# Schematic.net
KiCad netlist of a schematic drawn in EAGLE
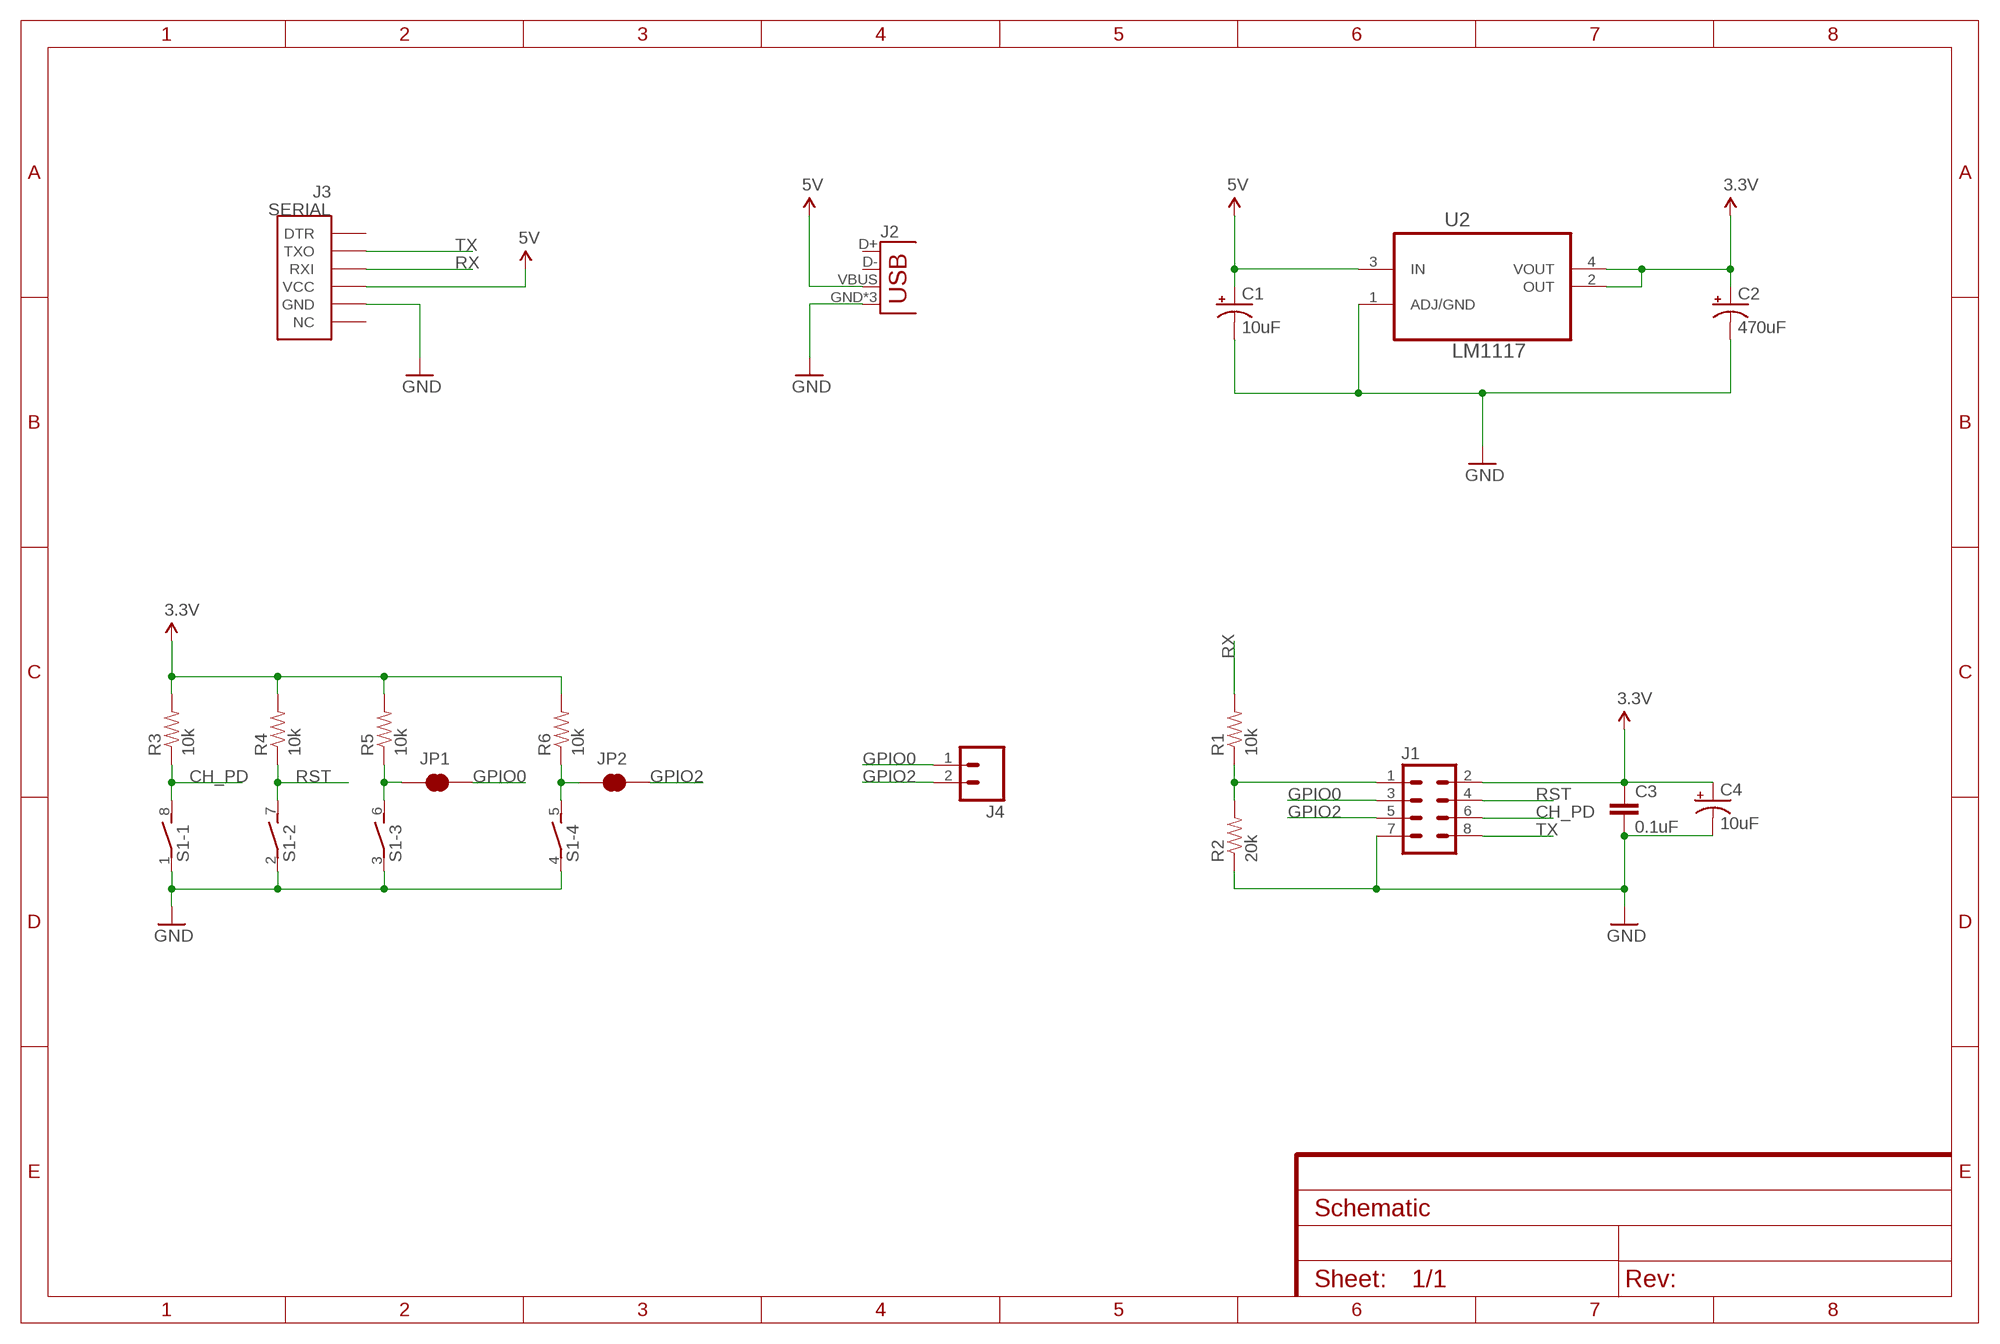
[diagram p0: schematic, sheet 1]

(export (version "E")
  (design (tool "Eeschema 10.0.6"))
  (components
    (comp (ref "C1")
      (value "10uF")
      (footprint "eagle-import:EIA3216-KIT")
      (libsource (lib "eagle-import") (part "CAP_POL1206-KIT"))
    )
    (comp (ref "C2")
      (value "470uF")
      (footprint "eagle-import:CPOL-RADIAL-100UF-25V")
      (libsource (lib "eagle-import") (part "CAP_POLPTH1"))
    )
    (comp (ref "C3")
      (value "0.1uF")
      (footprint "eagle-import:1206")
      (libsource (lib "eagle-import") (part "CAP1206"))
    )
    (comp (ref "C4")
      (value "10uF")
      (footprint "eagle-import:EIA3216-KIT")
      (libsource (lib "eagle-import") (part "CAP_POL1206-KIT"))
    )
    (comp (ref "J1")
      (value "M04X2")
      (footprint "eagle-import:2X4")
      (libsource (lib "eagle-import") (part "M04X2"))
    )
    (comp (ref "J2")
      (value "USB-MICROB")
      (footprint "eagle-import:USB-MICROB")
      (libsource (lib "eagle-import") (part "USB-MICROB"))
    )
    (comp (ref "J3")
      (value "SERIAL")
      (footprint "eagle-import:CP2102_DEVICE_SIDE")
      (libsource (lib "eagle-import") (part "CP2102_DEVICECP"))
    )
    (comp (ref "J4")
      (value "M02LOCK")
      (footprint "eagle-import:1X02_LOCK")
      (libsource (lib "eagle-import") (part "M02LOCK"))
    )
    (comp (ref "JP1")
      (value "JUMPER-PAD-2-NC_BY_TRACE")
      (footprint "eagle-import:PAD-JUMPER-2-NC_BY_TRACE_YES_SILK")
      (libsource (lib "eagle-import") (part "JUMPER-PAD-2-NC_BY_TRACE"))
    )
    (comp (ref "JP2")
      (value "JUMPER-PAD-2-NC_BY_TRACE")
      (footprint "eagle-import:PAD-JUMPER-2-NC_BY_TRACE_YES_SILK")
      (libsource (lib "eagle-import") (part "JUMPER-PAD-2-NC_BY_TRACE"))
    )
    (comp (ref "R1")
      (value "10k")
      (footprint "eagle-import:1206")
      (libsource (lib "eagle-import") (part "RESISTOR1206"))
    )
    (comp (ref "R2")
      (value "20k")
      (footprint "eagle-import:1206")
      (libsource (lib "eagle-import") (part "RESISTOR1206"))
    )
    (comp (ref "R3")
      (value "10k")
      (footprint "eagle-import:1206")
      (libsource (lib "eagle-import") (part "RESISTOR1206"))
    )
    (comp (ref "R4")
      (value "10k")
      (footprint "eagle-import:1206")
      (libsource (lib "eagle-import") (part "RESISTOR1206"))
    )
    (comp (ref "R5")
      (value "10k")
      (footprint "eagle-import:1206")
      (libsource (lib "eagle-import") (part "RESISTOR1206"))
    )
    (comp (ref "R6")
      (value "10k")
      (footprint "eagle-import:1206")
      (libsource (lib "eagle-import") (part "RESISTOR1206"))
    )
    (comp (ref "S1")
      (value "DIP04S")
      (footprint "eagle-import:DIP04S")
      (libsource (lib "eagle-import") (part "DIP04S"))
    )
    (comp (ref "U2")
      (value "LM1117")
      (footprint "eagle-import:SOT230P696X180-4N")
      (fields (field (name "MPN") "LM1117MP-3.3"))
      (libsource (lib "eagle-import") (part "LM1117MP-3.3"))
    )
  )
  (nets
    (net (code "1") (name "/CH_PD") (class "Default")
      (node (ref "J1") (pin "6") (pinfunction "6_6") (pintype "passive"))
      (node (ref "R3") (pin "1") (pinfunction "1_1") (pintype "passive"))
      (node (ref "S1") (pin "8") (pinfunction "2_8") (pintype "passive"))
    )
    (net (code "2") (name "/GPIO0") (class "Default")
      (node (ref "J1") (pin "3") (pinfunction "3_3") (pintype "passive"))
      (node (ref "J4") (pin "1") (pinfunction "1_1") (pintype "passive"))
      (node (ref "JP1") (pin "2") (pinfunction "2_2") (pintype "passive"))
    )
    (net (code "3") (name "/GPIO2") (class "Default")
      (node (ref "J1") (pin "5") (pinfunction "5_5") (pintype "passive"))
      (node (ref "J4") (pin "2") (pinfunction "2_2") (pintype "passive"))
      (node (ref "JP2") (pin "2") (pinfunction "2_2") (pintype "passive"))
    )
    (net (code "4") (name "/RST") (class "Default")
      (node (ref "J1") (pin "4") (pinfunction "4_4") (pintype "passive"))
      (node (ref "R4") (pin "1") (pinfunction "1_1") (pintype "passive"))
      (node (ref "S1") (pin "7") (pinfunction "2_7") (pintype "passive"))
    )
    (net (code "5") (name "/RX") (class "Default")
      (node (ref "J3") (pin "P$3") (pinfunction "RXI_P$3") (pintype "bidirectional"))
      (node (ref "R1") (pin "2") (pinfunction "2_2") (pintype "passive"))
    )
    (net (code "6") (name "/TX") (class "Default")
      (node (ref "J1") (pin "8") (pinfunction "8_8") (pintype "passive"))
      (node (ref "J3") (pin "P$2") (pinfunction "TXO_P$2") (pintype "bidirectional"))
    )
    (net (code "7") (name "3.3V") (class "Default")
      (node (ref "C2") (pin "1") (pinfunction "+_1") (pintype "passive"))
      (node (ref "C3") (pin "1") (pinfunction "1_1") (pintype "passive"))
      (node (ref "C4") (pin "A") (pinfunction "+_A") (pintype "passive"))
      (node (ref "J1") (pin "2") (pinfunction "2_2") (pintype "passive"))
      (node (ref "R3") (pin "2") (pinfunction "2_2") (pintype "passive"))
      (node (ref "R4") (pin "2") (pinfunction "2_2") (pintype "passive"))
      (node (ref "R5") (pin "2") (pinfunction "2_2") (pintype "passive"))
      (node (ref "R6") (pin "2") (pinfunction "2_2") (pintype "passive"))
      (node (ref "U2") (pin "2") (pinfunction "OUT_2") (pintype "output"))
      (node (ref "U2") (pin "4") (pinfunction "VOUT_4") (pintype "output"))
    )
    (net (code "8") (name "5V") (class "Default")
      (node (ref "C1") (pin "A") (pinfunction "+_A") (pintype "passive"))
      (node (ref "J2") (pin "VBUS") (pinfunction "VBUS_VBUS") (pintype "bidirectional"))
      (node (ref "J3") (pin "P$4") (pinfunction "VCC_P$4") (pintype "bidirectional"))
      (node (ref "U2") (pin "3") (pinfunction "IN_3") (pintype "input"))
    )
    (net (code "9") (name "GND") (class "Default")
      (node (ref "C1") (pin "C") (pinfunction "-_C") (pintype "passive"))
      (node (ref "C2") (pin "2") (pinfunction "-_2") (pintype "passive"))
      (node (ref "C3") (pin "2") (pinfunction "2_2") (pintype "passive"))
      (node (ref "C4") (pin "C") (pinfunction "-_C") (pintype "passive"))
      (node (ref "J1") (pin "7") (pinfunction "7_7") (pintype "passive"))
      (node (ref "J2") (pin "GND") (pinfunction "GND_GND") (pintype "bidirectional"))
      (node (ref "J2") (pin "MT1") (pinfunction "GND_MT1") (pintype "bidirectional"))
      (node (ref "J2") (pin "MT2") (pinfunction "GND_MT2") (pintype "bidirectional"))
      (node (ref "J3") (pin "P$5") (pinfunction "GND_P$5") (pintype "bidirectional"))
      (node (ref "R2") (pin "1") (pinfunction "1_1") (pintype "passive"))
      (node (ref "S1") (pin "1") (pinfunction "1_1") (pintype "passive"))
      (node (ref "S1") (pin "2") (pinfunction "1_2") (pintype "passive"))
      (node (ref "S1") (pin "3") (pinfunction "1_3") (pintype "passive"))
      (node (ref "S1") (pin "4") (pinfunction "1_4") (pintype "passive"))
      (node (ref "U2") (pin "1") (pinfunction "ADJ/GND_1") (pintype "passive"))
    )
    (net (code "10") (name "Net-(J1-Pad1)") (class "Default")
      (node (ref "J1") (pin "1") (pinfunction "1_1") (pintype "passive"))
      (node (ref "R1") (pin "1") (pinfunction "1_1") (pintype "passive"))
      (node (ref "R2") (pin "2") (pinfunction "2_2") (pintype "passive"))
    )
    (net (code "11") (name "Net-(S1C-2)") (class "Default")
      (node (ref "JP1") (pin "1") (pinfunction "1_1") (pintype "passive"))
      (node (ref "R5") (pin "1") (pinfunction "1_1") (pintype "passive"))
      (node (ref "S1") (pin "6") (pinfunction "2_6") (pintype "passive"))
    )
    (net (code "12") (name "Net-(S1D-2)") (class "Default")
      (node (ref "JP2") (pin "1") (pinfunction "1_1") (pintype "passive"))
      (node (ref "R6") (pin "1") (pinfunction "1_1") (pintype "passive"))
      (node (ref "S1") (pin "5") (pinfunction "2_5") (pintype "passive"))
    )
    (net (code "13") (name "unconnected-(J2-PadD+)") (class "Default")
      (node (ref "J2") (pin "D+") (pinfunction "D+_D+") (pintype "bidirectional"))
    )
    (net (code "14") (name "unconnected-(J2-PadD-)") (class "Default")
      (node (ref "J2") (pin "D-") (pinfunction "D-_D-") (pintype "bidirectional"))
    )
    (net (code "15") (name "unconnected-(J3-DTR-PadP$1)") (class "Default")
      (node (ref "J3") (pin "P$1") (pinfunction "DTR_P$1") (pintype "bidirectional"))
    )
    (net (code "16") (name "unconnected-(J3-NC-PadP$6)") (class "Default")
      (node (ref "J3") (pin "P$6") (pinfunction "NC_P$6") (pintype "bidirectional"))
    )
  )
)
